# PLD_Connectors.net
KiCad netlist of a schematic drawn in Altium Designer
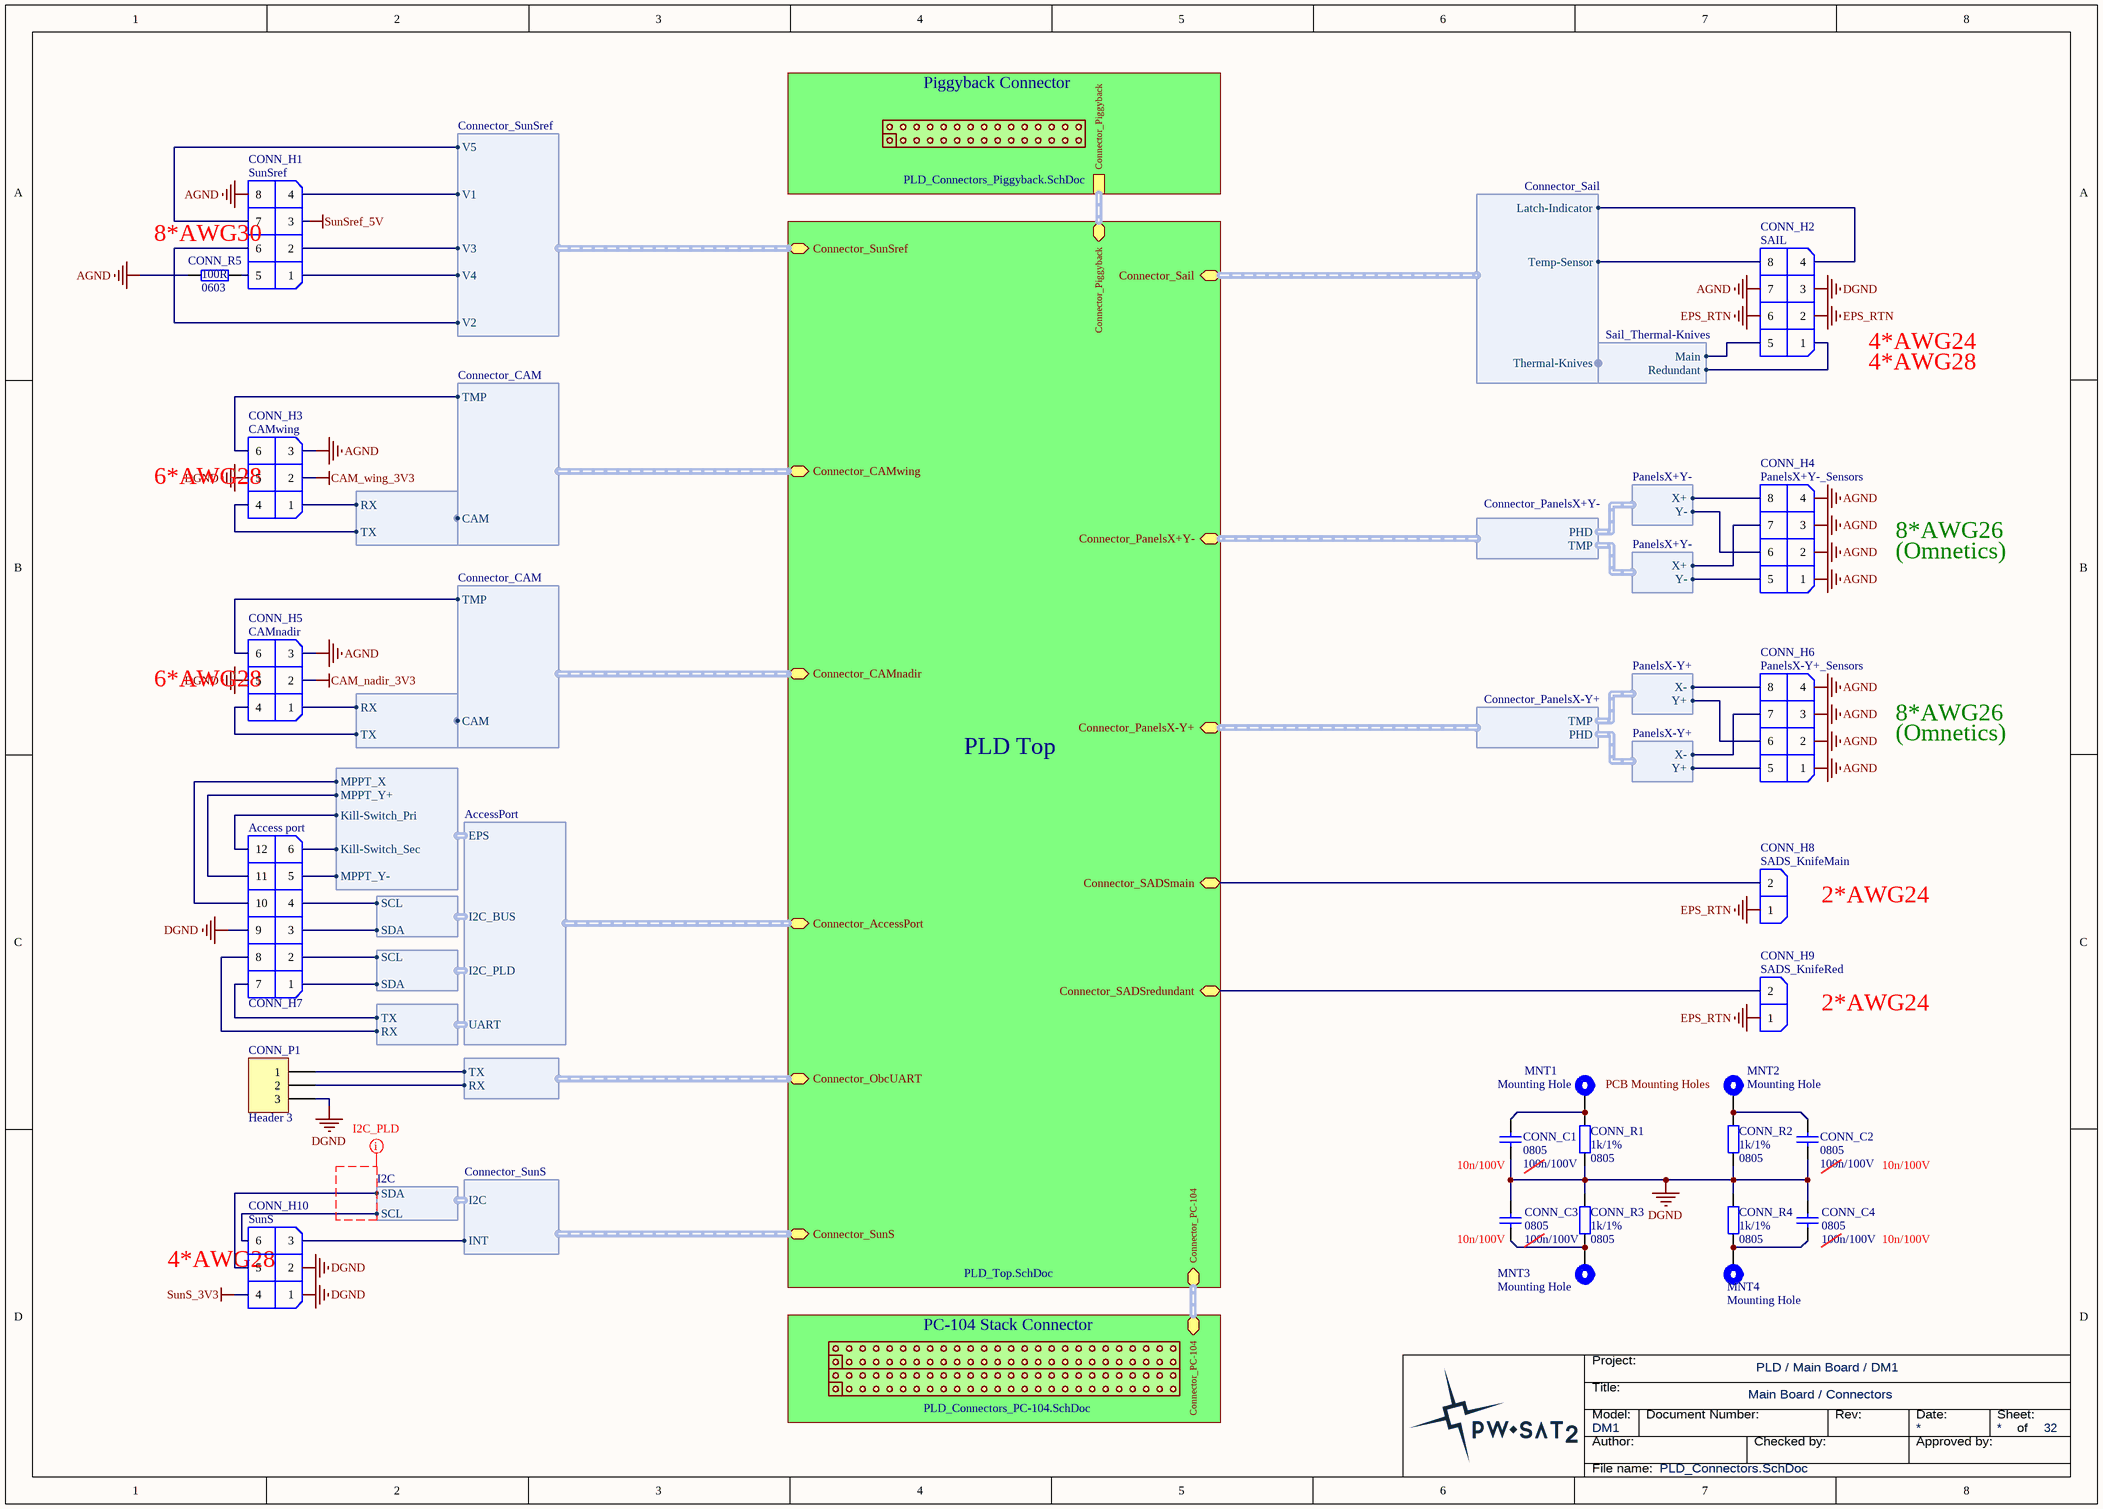
[diagram p0: PLD_Connectors.SchDoc]

(export (version "E")
  (design (tool "Eeschema 10.0.6"))
  (components
    (comp (ref "CONN_C1")
      (value "100n/100V")
      (footprint "SMD_Capacitor_0805")
      (description "Ceramic Cap Kemet COTS 100n/100V X7R 0805")
      (fields
        (field (name "MANUFACTURERPARTNUMBER") "C0805T104K1RCLTU")
        (field (name "MANUFACTURER") "Kemet")
        (field (name "PACKAGE") "0805")
      )
      (libsource (lib "capacitors") (part "Cer_C0805T104K1RCLTU"))
    )
    (comp (ref "CONN_C2")
      (value "100n/100V")
      (footprint "SMD_Capacitor_0805")
      (description "Ceramic Cap Kemet COTS 100n/100V X7R 0805")
      (fields
        (field (name "MANUFACTURERPARTNUMBER") "C0805T104K1RCLTU")
        (field (name "MANUFACTURER") "Kemet")
        (field (name "PACKAGE") "0805")
      )
      (libsource (lib "capacitors") (part "Cer_C0805T104K1RCLTU"))
    )
    (comp (ref "CONN_C3")
      (value "100n/100V")
      (footprint "SMD_Capacitor_0805")
      (description "Ceramic Cap Kemet COTS 100n/100V X7R 0805")
      (fields
        (field (name "MANUFACTURERPARTNUMBER") "C0805T104K1RCLTU")
        (field (name "MANUFACTURER") "Kemet")
        (field (name "PACKAGE") "0805")
      )
      (libsource (lib "capacitors") (part "Cer_C0805T104K1RCLTU"))
    )
    (comp (ref "CONN_C4")
      (value "100n/100V")
      (footprint "SMD_Capacitor_0805")
      (description "Ceramic Cap Kemet COTS 100n/100V X7R 0805")
      (fields
        (field (name "MANUFACTURERPARTNUMBER") "C0805T104K1RCLTU")
        (field (name "MANUFACTURER") "Kemet")
        (field (name "PACKAGE") "0805")
      )
      (libsource (lib "capacitors") (part "Cer_C0805T104K1RCLTU"))
    )
    (comp (ref "CONN_H1")
      (value "SunSref")
      (footprint "Harwin_Datamate_L-Tek_M80-8670805")
      (description "Harwin DataMate L-Tek, 2mm pitch, 2x4pin.")
      (libsource (lib "connectors_printed-circuit-board") (part "Harwin_Datamate_L-Tek_2x4pin"))
    )
    (comp (ref "CONN_H2")
      (value "SAIL")
      (footprint "Harwin_Datamate_L-Tek_M80-8670805")
      (description "Harwin DataMate L-Tek, 2mm pitch, 2x4pin.")
      (libsource (lib "connectors_printed-circuit-board") (part "Harwin_Datamate_L-Tek_2x4pin"))
    )
    (comp (ref "CONN_H3")
      (value "CAMwing")
      (footprint "Harwin_Datamate_L-Tek_M80-8670605")
      (description "Harwin DataMate L-Tek, 2mm pitch, 2x3pin.")
      (libsource (lib "connectors_printed-circuit-board") (part "Harwin_Datamate_L-Tek_2x3pin"))
    )
    (comp (ref "CONN_H4")
      (value "PanelsX+Y-_Sensors")
      (footprint "Harwin_Datamate_L-Tek_M80-8670805")
      (description "Harwin DataMate L-Tek, 2mm pitch, 2x4pin.")
      (libsource (lib "connectors_printed-circuit-board") (part "Harwin_Datamate_L-Tek_2x4pin"))
    )
    (comp (ref "CONN_H5")
      (value "CAMnadir")
      (footprint "Harwin_Datamate_L-Tek_M80-8670605")
      (description "Harwin DataMate L-Tek, 2mm pitch, 2x3pin.")
      (libsource (lib "connectors_printed-circuit-board") (part "Harwin_Datamate_L-Tek_2x3pin"))
    )
    (comp (ref "CONN_H6")
      (value "PanelsX-Y+_Sensors")
      (footprint "Harwin_Datamate_L-Tek_M80-8670805")
      (description "Harwin DataMate L-Tek, 2mm pitch, 2x4pin.")
      (libsource (lib "connectors_printed-circuit-board") (part "Harwin_Datamate_L-Tek_2x4pin"))
    )
    (comp (ref "CONN_H7")
      (value "Access port")
      (footprint "Harwin_Datamate_L-Tek_M80-8411242")
      (description "Harwin DataMate L-Tek, 2mm pitch, 2x6pin.")
      (libsource (lib "connectors_printed-circuit-board") (part "Harwin_Datamate_L-Tek_2x6pin"))
    )
    (comp (ref "CONN_H8")
      (value "SADS_KnifeMain")
      (footprint "Harwin_Datamate_L-Tek_M80-8770222")
      (description "Harwin DataMate L-Tek, 2mm pitch, 1x2pin.")
      (libsource (lib "connectors_printed-circuit-board") (part "Harwin_Datamate_L-Tek_1x2pin"))
    )
    (comp (ref "CONN_H9")
      (value "SADS_KnifeRed")
      (footprint "Harwin_Datamate_L-Tek_M80-8770222")
      (description "Harwin DataMate L-Tek, 2mm pitch, 1x2pin.")
      (libsource (lib "connectors_printed-circuit-board") (part "Harwin_Datamate_L-Tek_1x2pin"))
    )
    (comp (ref "CONN_H10")
      (value "SunS")
      (footprint "Harwin_Datamate_L-Tek_M80-8670605")
      (description "Harwin DataMate L-Tek, 2mm pitch, 2x3pin.")
      (libsource (lib "connectors_printed-circuit-board") (part "Harwin_Datamate_L-Tek_2x3pin"))
    )
    (comp (ref "CONN_P1")
      (value "Header 3")
      (footprint "HEADER 1X3 FEMALE")
      (description "Header, 3-Pin")
      (fields (field (name "PUBLISHER") "Altium Limited"))
      (libsource (lib "connectors_printed-circuit-board") (part "Header 3"))
    )
    (comp (ref "CONN_R1")
      (value "1k/1%")
      (footprint "SMD_Resistor_0805")
      (description "1k/1% Vishay CRCW 0805 Resistor. 125mW, 100ppm, 150V.")
      (fields
        (field (name "MANUFACTURER") "Vishay")
        (field (name "MANUFACTURERPARTNUMBER") "CRCW08051K00FKxxxx")
        (field (name "PACKAGE") "0805")
      )
      (libsource (lib "") (part "CRCW08051K00FKxxxx_1"))
    )
    (comp (ref "CONN_R2")
      (value "1k/1%")
      (footprint "SMD_Resistor_0805")
      (description "1k/1% Vishay CRCW 0805 Resistor. 125mW, 100ppm, 150V.")
      (fields
        (field (name "MANUFACTURER") "Vishay")
        (field (name "MANUFACTURERPARTNUMBER") "CRCW08051K00FKxxxx")
        (field (name "PACKAGE") "0805")
      )
      (libsource (lib "resistors") (part "CRCW08051K00FKxxxx"))
    )
    (comp (ref "CONN_R3")
      (value "1k/1%")
      (footprint "SMD_Resistor_0805")
      (description "1k/1% Vishay CRCW 0805 Resistor. 125mW, 100ppm, 150V.")
      (fields
        (field (name "MANUFACTURER") "Vishay")
        (field (name "MANUFACTURERPARTNUMBER") "CRCW08051K00FKxxxx")
        (field (name "PACKAGE") "0805")
      )
      (libsource (lib "") (part "CRCW08051K00FKxxxx_1"))
    )
    (comp (ref "CONN_R4")
      (value "1k/1%")
      (footprint "SMD_Resistor_0805")
      (description "1k/1% Vishay CRCW 0805 Resistor. 125mW, 100ppm, 150V.")
      (fields
        (field (name "MANUFACTURER") "Vishay")
        (field (name "MANUFACTURERPARTNUMBER") "CRCW08051K00FKxxxx")
        (field (name "PACKAGE") "0805")
      )
      (libsource (lib "resistors") (part "CRCW08051K00FKxxxx"))
    )
    (comp (ref "CONN_R5")
      (value "100R")
      (footprint "SMD_Resistor_0603")
      (fields (field (name "PACKAGE") "0603"))
      (libsource (lib "resistors") (part "Res"))
    )
    (comp (ref "MNT1")
      (value "Mounting Hole")
      (footprint "PC-104_PcbMntHole_M3")
      (description "PCB Mounting Hole")
      (libsource (lib "connectors_printed-circuit-board") (part "MntHole"))
    )
    (comp (ref "MNT2")
      (value "Mounting Hole")
      (footprint "PC-104_PcbMntHole_M3")
      (description "PCB Mounting Hole")
      (libsource (lib "connectors_printed-circuit-board") (part "MntHole"))
    )
    (comp (ref "MNT3")
      (value "Mounting Hole")
      (footprint "PC-104_PcbMntHole_M3")
      (description "PCB Mounting Hole")
      (libsource (lib "connectors_printed-circuit-board") (part "MntHole"))
    )
    (comp (ref "MNT4")
      (value "Mounting Hole")
      (footprint "PC-104_PcbMntHole_M3")
      (description "PCB Mounting Hole")
      (libsource (lib "connectors_printed-circuit-board") (part "MntHole"))
    )
  )
  (nets
    (net (code "16") (name "/Connector_SADSmain") (class "Default")
      (node (ref "CONN_H8") (pin "2") (pinfunction "2_2") (pintype "passive"))
    )
    (net (code "17") (name "/Connector_SADSredundant") (class "Default")
      (node (ref "CONN_H9") (pin "2") (pinfunction "2_2") (pintype "passive"))
    )
    (net (code "18") (name "/INT") (class "Default")
      (node (ref "CONN_H10") (pin "3") (pinfunction "3_3") (pintype "passive"))
    )
    (net (code "19") (name "/Kill-Switch_Pri") (class "Default")
      (node (ref "CONN_H7") (pin "12") (pinfunction "12_12") (pintype "passive"))
    )
    (net (code "20") (name "/Kill-Switch_Sec") (class "Default")
      (node (ref "CONN_H7") (pin "6") (pinfunction "6_6") (pintype "passive"))
    )
    (net (code "21") (name "/Latch-Indicator") (class "Default")
      (node (ref "CONN_H2") (pin "4") (pinfunction "4_4") (pintype "passive"))
    )
    (net (code "22") (name "/MPPT_X") (class "Default")
      (node (ref "CONN_H7") (pin "10") (pinfunction "10_10") (pintype "passive"))
    )
    (net (code "23") (name "/MPPT_Y+") (class "Default")
      (node (ref "CONN_H7") (pin "11") (pinfunction "11_11") (pintype "passive"))
    )
    (net (code "24") (name "/MPPT_Y-") (class "Default")
      (node (ref "CONN_H7") (pin "5") (pinfunction "5_5") (pintype "passive"))
    )
    (net (code "25") (name "/Main") (class "Default")
      (node (ref "CONN_H2") (pin "5") (pinfunction "5_5") (pintype "passive"))
    )
    (net (code "26") (name "/Redundant") (class "Default")
      (node (ref "CONN_H2") (pin "1") (pinfunction "1_1") (pintype "passive"))
    )
    (net (code "27") (name "/Temp-Sensor") (class "Default")
      (node (ref "CONN_H2") (pin "8") (pinfunction "8_8") (pintype "passive"))
    )
    (net (code "28") (name "/V1") (class "Default")
      (node (ref "CONN_H1") (pin "4") (pinfunction "4_4") (pintype "passive"))
    )
    (net (code "29") (name "/V2") (class "Default")
      (node (ref "CONN_H1") (pin "6") (pinfunction "6_6") (pintype "passive"))
    )
    (net (code "30") (name "/V3") (class "Default")
      (node (ref "CONN_H1") (pin "2") (pinfunction "2_2") (pintype "passive"))
    )
    (net (code "31") (name "/V4") (class "Default")
      (node (ref "CONN_H1") (pin "1") (pinfunction "1_1") (pintype "passive"))
    )
    (net (code "32") (name "/V5") (class "Default")
      (node (ref "CONN_H1") (pin "7") (pinfunction "7_7") (pintype "passive"))
    )
    (net (code "43") (name "AGND") (class "Default")
      (node (ref "CONN_H1") (pin "8") (pinfunction "8_8") (pintype "passive"))
      (node (ref "CONN_H2") (pin "7") (pinfunction "7_7") (pintype "passive"))
      (node (ref "CONN_H3") (pin "3") (pinfunction "3_3") (pintype "passive"))
      (node (ref "CONN_H4") (pin "1") (pinfunction "1_1") (pintype "passive"))
      (node (ref "CONN_H4") (pin "2") (pinfunction "2_2") (pintype "passive"))
      (node (ref "CONN_H4") (pin "3") (pinfunction "3_3") (pintype "passive"))
      (node (ref "CONN_H4") (pin "4") (pinfunction "4_4") (pintype "passive"))
      (node (ref "CONN_H5") (pin "3") (pinfunction "3_3") (pintype "passive"))
      (node (ref "CONN_H6") (pin "1") (pinfunction "1_1") (pintype "passive"))
      (node (ref "CONN_H6") (pin "2") (pinfunction "2_2") (pintype "passive"))
      (node (ref "CONN_H6") (pin "3") (pinfunction "3_3") (pintype "passive"))
      (node (ref "CONN_H6") (pin "4") (pinfunction "4_4") (pintype "passive"))
      (node (ref "CONN_R5") (pin "1") (pinfunction "1_1") (pintype "passive"))
    )
    (net (code "44") (name "CAM_nadir_3V3") (class "Default")
      (node (ref "CONN_H5") (pin "2") (pinfunction "2_2") (pintype "passive"))
    )
    (net (code "45") (name "CAM_wing_3V3") (class "Default")
      (node (ref "CONN_H3") (pin "2") (pinfunction "2_2") (pintype "passive"))
    )
    (net (code "46") (name "DGND") (class "Default")
      (node (ref "CONN_C1") (pin "1") (pinfunction "1_1") (pintype "passive"))
      (node (ref "CONN_C2") (pin "1") (pinfunction "1_1") (pintype "passive"))
      (node (ref "CONN_C3") (pin "2") (pinfunction "2_2") (pintype "passive"))
      (node (ref "CONN_C4") (pin "2") (pinfunction "2_2") (pintype "passive"))
      (node (ref "CONN_H10") (pin "1") (pinfunction "1_1") (pintype "passive"))
      (node (ref "CONN_H10") (pin "2") (pinfunction "2_2") (pintype "passive"))
      (node (ref "CONN_H2") (pin "3") (pinfunction "3_3") (pintype "passive"))
      (node (ref "CONN_H3") (pin "5") (pinfunction "5_5") (pintype "passive"))
      (node (ref "CONN_H5") (pin "5") (pinfunction "5_5") (pintype "passive"))
      (node (ref "CONN_H7") (pin "9") (pinfunction "9_9") (pintype "passive"))
      (node (ref "CONN_P1") (pin "3") (pinfunction "3_3") (pintype "passive"))
      (node (ref "CONN_R1") (pin "1") (pinfunction "1_1") (pintype "passive"))
      (node (ref "CONN_R2") (pin "1") (pinfunction "1_1") (pintype "passive"))
      (node (ref "CONN_R3") (pin "2") (pinfunction "2_2") (pintype "passive"))
      (node (ref "CONN_R4") (pin "2") (pinfunction "2_2") (pintype "passive"))
    )
    (net (code "47") (name "EPS_RTN") (class "Default")
      (node (ref "CONN_H2") (pin "2") (pinfunction "2_2") (pintype "passive"))
      (node (ref "CONN_H2") (pin "6") (pinfunction "6_6") (pintype "passive"))
      (node (ref "CONN_H8") (pin "1") (pinfunction "1_1") (pintype "passive"))
      (node (ref "CONN_H9") (pin "1") (pinfunction "1_1") (pintype "passive"))
    )
    (net (code "48") (name "Net-(CONN_C1-Pad2)") (class "Default")
      (node (ref "CONN_C1") (pin "2") (pinfunction "2_2") (pintype "passive"))
      (node (ref "CONN_R1") (pin "2") (pinfunction "2_2") (pintype "passive"))
      (node (ref "MNT1") (pin "1") (pinfunction "1_1") (pintype "passive"))
    )
    (net (code "49") (name "Net-(CONN_C2-Pad2)") (class "Default")
      (node (ref "CONN_C2") (pin "2") (pinfunction "2_2") (pintype "passive"))
      (node (ref "CONN_R2") (pin "2") (pinfunction "2_2") (pintype "passive"))
      (node (ref "MNT2") (pin "1") (pinfunction "1_1") (pintype "passive"))
    )
    (net (code "50") (name "Net-(CONN_C3-Pad1)") (class "Default")
      (node (ref "CONN_C3") (pin "1") (pinfunction "1_1") (pintype "passive"))
      (node (ref "CONN_R3") (pin "1") (pinfunction "1_1") (pintype "passive"))
      (node (ref "MNT3") (pin "1") (pinfunction "1_1") (pintype "passive"))
    )
    (net (code "51") (name "Net-(CONN_C4-Pad1)") (class "Default")
      (node (ref "CONN_C4") (pin "1") (pinfunction "1_1") (pintype "passive"))
      (node (ref "CONN_R4") (pin "1") (pinfunction "1_1") (pintype "passive"))
      (node (ref "MNT4") (pin "1") (pinfunction "1_1") (pintype "passive"))
    )
    (net (code "52") (name "Net-(CONN_H1-Pad5)") (class "Default")
      (node (ref "CONN_H1") (pin "5") (pinfunction "5_5") (pintype "passive"))
      (node (ref "CONN_R5") (pin "2") (pinfunction "2_2") (pintype "passive"))
    )
    (net (code "53") (name "SunS_3V3") (class "Default")
      (node (ref "CONN_H10") (pin "4") (pinfunction "4_4") (pintype "passive"))
    )
    (net (code "54") (name "SunSref_5V") (class "Default")
      (node (ref "CONN_H1") (pin "3") (pinfunction "3_3") (pintype "passive"))
    )
    (net (code "55") (name "unconnected-(CONN_H3-Pad1)") (class "Default")
      (node (ref "CONN_H3") (pin "1") (pinfunction "1_1") (pintype "passive"))
    )
    (net (code "56") (name "unconnected-(CONN_H3-Pad4)") (class "Default")
      (node (ref "CONN_H3") (pin "4") (pinfunction "4_4") (pintype "passive"))
    )
    (net (code "57") (name "unconnected-(CONN_H3-Pad6)") (class "Default")
      (node (ref "CONN_H3") (pin "6") (pinfunction "6_6") (pintype "passive"))
    )
    (net (code "58") (name "unconnected-(CONN_H4-Pad5)") (class "Default")
      (node (ref "CONN_H4") (pin "5") (pinfunction "5_5") (pintype "passive"))
    )
    (net (code "59") (name "unconnected-(CONN_H4-Pad6)") (class "Default")
      (node (ref "CONN_H4") (pin "6") (pinfunction "6_6") (pintype "passive"))
    )
    (net (code "60") (name "unconnected-(CONN_H4-Pad7)") (class "Default")
      (node (ref "CONN_H4") (pin "7") (pinfunction "7_7") (pintype "passive"))
    )
    (net (code "61") (name "unconnected-(CONN_H4-Pad8)") (class "Default")
      (node (ref "CONN_H4") (pin "8") (pinfunction "8_8") (pintype "passive"))
    )
    (net (code "62") (name "unconnected-(CONN_H5-Pad1)") (class "Default")
      (node (ref "CONN_H5") (pin "1") (pinfunction "1_1") (pintype "passive"))
    )
    (net (code "63") (name "unconnected-(CONN_H5-Pad4)") (class "Default")
      (node (ref "CONN_H5") (pin "4") (pinfunction "4_4") (pintype "passive"))
    )
    (net (code "64") (name "unconnected-(CONN_H5-Pad6)") (class "Default")
      (node (ref "CONN_H5") (pin "6") (pinfunction "6_6") (pintype "passive"))
    )
    (net (code "65") (name "unconnected-(CONN_H6-Pad5)") (class "Default")
      (node (ref "CONN_H6") (pin "5") (pinfunction "5_5") (pintype "passive"))
    )
    (net (code "66") (name "unconnected-(CONN_H6-Pad6)") (class "Default")
      (node (ref "CONN_H6") (pin "6") (pinfunction "6_6") (pintype "passive"))
    )
    (net (code "67") (name "unconnected-(CONN_H6-Pad7)") (class "Default")
      (node (ref "CONN_H6") (pin "7") (pinfunction "7_7") (pintype "passive"))
    )
    (net (code "68") (name "unconnected-(CONN_H6-Pad8)") (class "Default")
      (node (ref "CONN_H6") (pin "8") (pinfunction "8_8") (pintype "passive"))
    )
    (net (code "69") (name "unconnected-(CONN_H7-Pad1)") (class "Default")
      (node (ref "CONN_H7") (pin "1") (pinfunction "1_1") (pintype "passive"))
    )
    (net (code "70") (name "unconnected-(CONN_H7-Pad2)") (class "Default")
      (node (ref "CONN_H7") (pin "2") (pinfunction "2_2") (pintype "passive"))
    )
    (net (code "71") (name "unconnected-(CONN_H7-Pad3)") (class "Default")
      (node (ref "CONN_H7") (pin "3") (pinfunction "3_3") (pintype "passive"))
    )
    (net (code "72") (name "unconnected-(CONN_H7-Pad4)") (class "Default")
      (node (ref "CONN_H7") (pin "4") (pinfunction "4_4") (pintype "passive"))
    )
    (net (code "73") (name "unconnected-(CONN_H7-Pad7)") (class "Default")
      (node (ref "CONN_H7") (pin "7") (pinfunction "7_7") (pintype "passive"))
    )
    (net (code "74") (name "unconnected-(CONN_H7-Pad8)") (class "Default")
      (node (ref "CONN_H7") (pin "8") (pinfunction "8_8") (pintype "passive"))
    )
    (net (code "75") (name "unconnected-(CONN_H10-Pad5)") (class "Default")
      (node (ref "CONN_H10") (pin "5") (pinfunction "5_5") (pintype "passive"))
    )
    (net (code "76") (name "unconnected-(CONN_H10-Pad6)") (class "Default")
      (node (ref "CONN_H10") (pin "6") (pinfunction "6_6") (pintype "passive"))
    )
    (net (code "77") (name "unconnected-(CONN_P1-Pad1)") (class "Default")
      (node (ref "CONN_P1") (pin "1") (pinfunction "1_1") (pintype "passive"))
    )
    (net (code "78") (name "unconnected-(CONN_P1-Pad2)") (class "Default")
      (node (ref "CONN_P1") (pin "2") (pinfunction "2_2") (pintype "passive"))
    )
  )
)
